# BBB_SCH2.net
KiCad netlist of a schematic drawn in Altium Designer
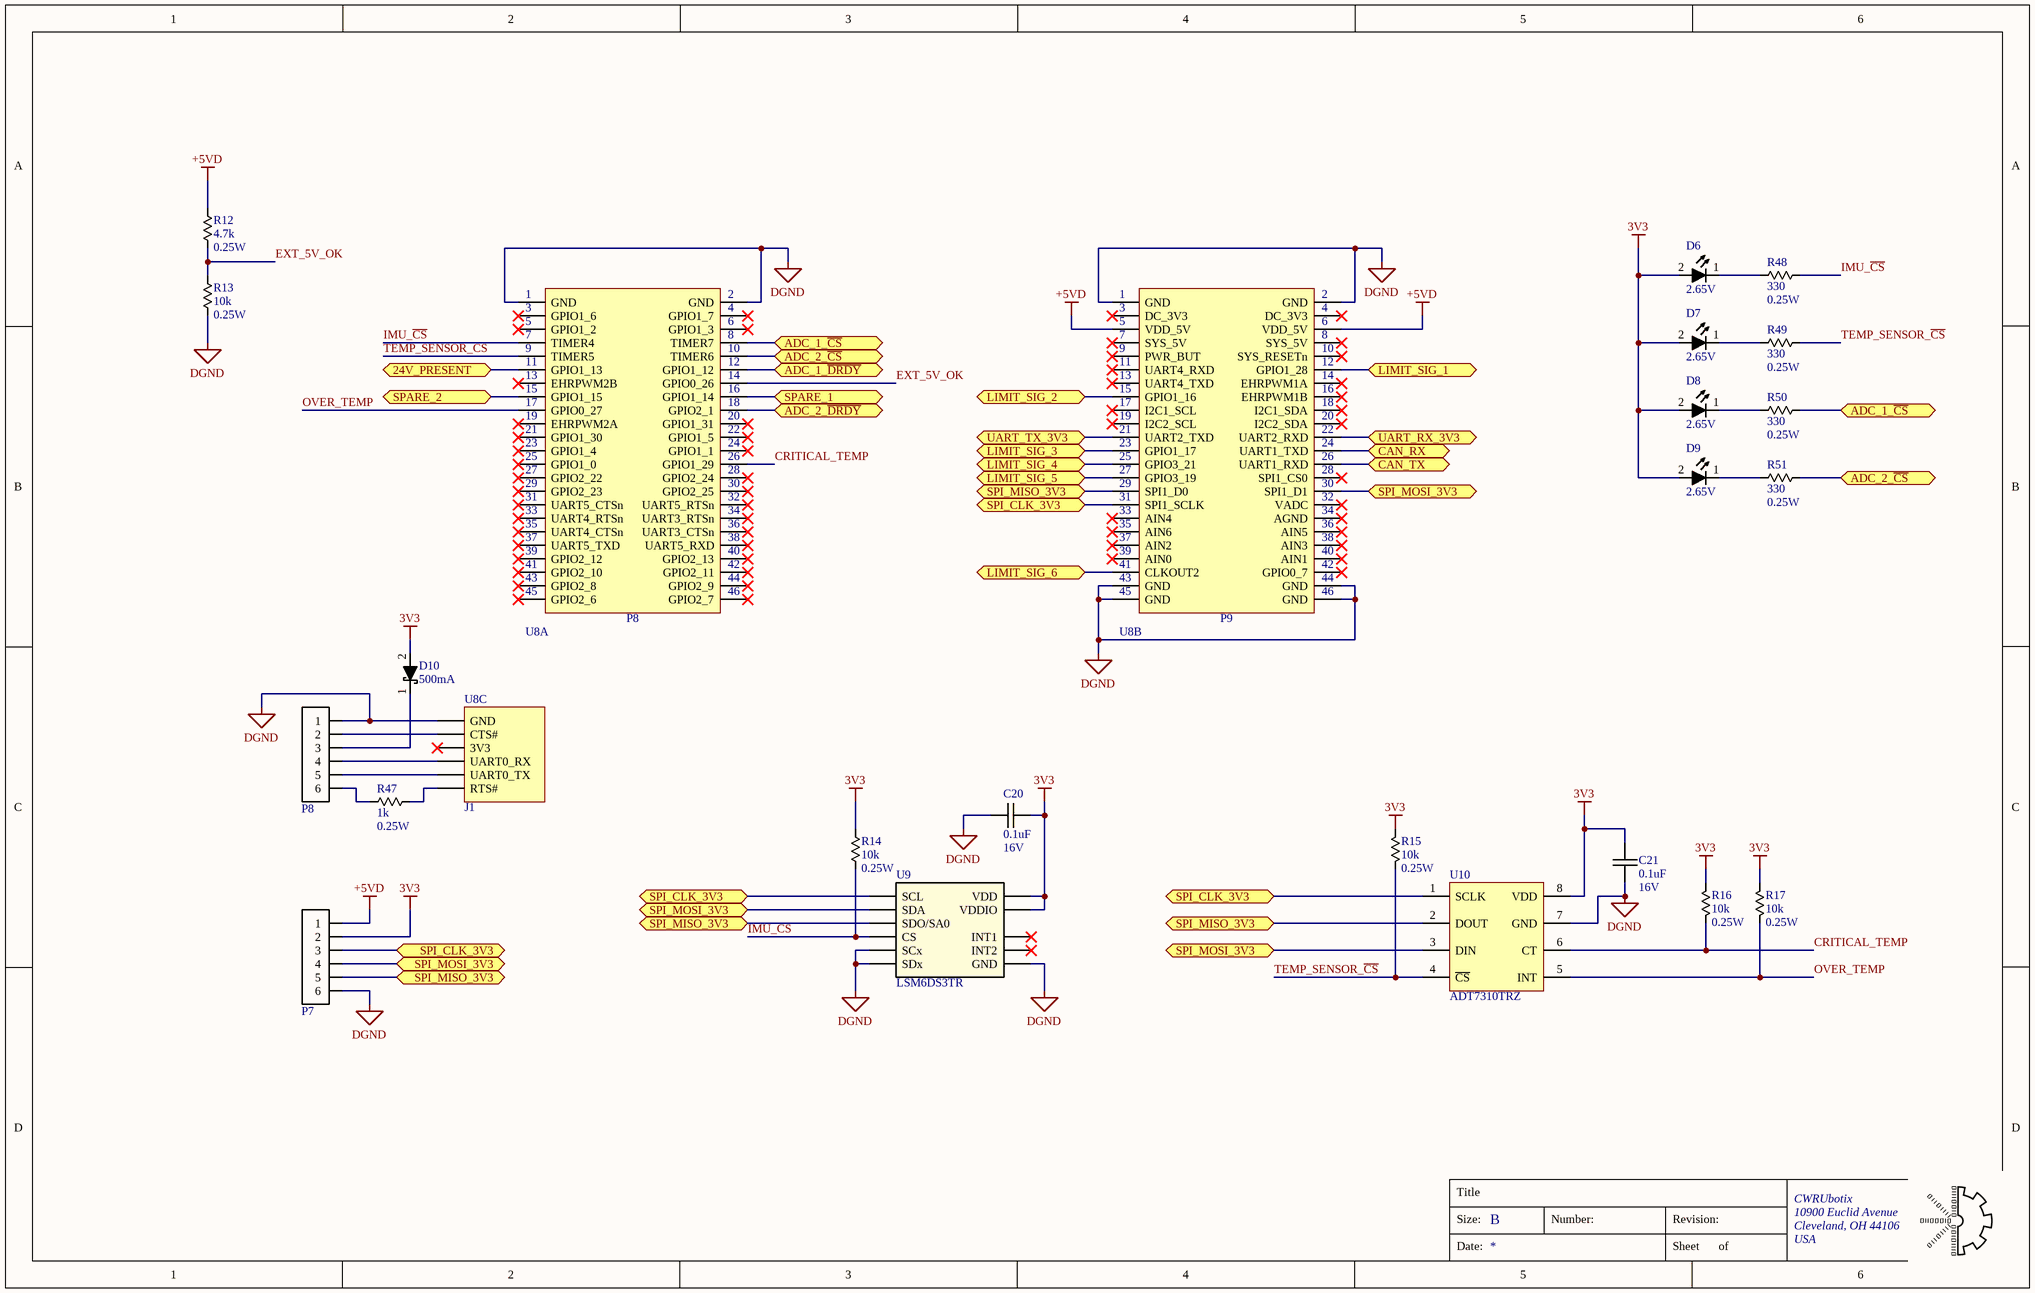
[diagram p0: BBB_SCH2.SchDoc]

(export (version "E")
  (design (tool "Eeschema 10.0.6"))
  (components
    (comp (ref "C20")
      (value "cap_single_np")
      (footprint "chip_0603")
      (description "CAP, 0.1uF, ±10%, 16V, X7R, 0603")
      (fields
        (field (name "TOLERANCE") "±10%")
        (field (name "CAPACITANCE") "0.1uF")
        (field (name "VOLTAGE RATING") "16V")
        (field (name "PART NUMBER") "CAP-00542")
      )
      (libsource (lib "Capacitors") (part "cap_single_np"))
    )
    (comp (ref "C21")
      (value "cap_single_np")
      (footprint "chip_0603")
      (description "CAP, 0.1uF, ±10%, 16V, X7R, 0603")
      (fields
        (field (name "TOLERANCE") "±10%")
        (field (name "CAPACITANCE") "0.1uF")
        (field (name "VOLTAGE RATING") "16V")
        (field (name "PART NUMBER") "CAP-00542")
      )
      (libsource (lib "Capacitors") (part "cap_single_np"))
    )
    (comp (ref "D6")
      (value "diode_4")
      (footprint "chip_0603")
      (description "LED, Blue, 0603, Low current, HELI2 Series")
      (fields
        (field (name "FORWARD VOLTAGE") "2.65V")
        (field (name "PART NUMBER") "DIO-00049")
        (field (name "MANUFACTURER") "Kingbright")
      )
      (libsource (lib "Diodes") (part "diode_4"))
    )
    (comp (ref "D7")
      (value "diode_4")
      (footprint "chip_0603")
      (description "LED, Blue, 0603, Low current, HELI2 Series")
      (fields
        (field (name "FORWARD VOLTAGE") "2.65V")
        (field (name "PART NUMBER") "DIO-00049")
        (field (name "MANUFACTURER") "Kingbright")
      )
      (libsource (lib "Diodes") (part "diode_4"))
    )
    (comp (ref "D8")
      (value "diode_4")
      (footprint "chip_0603")
      (description "LED, Blue, 0603, Low current, HELI2 Series")
      (fields
        (field (name "FORWARD VOLTAGE") "2.65V")
        (field (name "PART NUMBER") "DIO-00049")
        (field (name "MANUFACTURER") "Kingbright")
      )
      (libsource (lib "Diodes") (part "diode_4"))
    )
    (comp (ref "D9")
      (value "diode_4")
      (footprint "chip_0603")
      (description "LED, Blue, 0603, Low current, HELI2 Series")
      (fields
        (field (name "FORWARD VOLTAGE") "2.65V")
        (field (name "PART NUMBER") "DIO-00049")
        (field (name "MANUFACTURER") "Kingbright")
      )
      (libsource (lib "Diodes") (part "diode_4"))
    )
    (comp (ref "D10")
      (value "diode_2")
      (footprint "sod323_0")
      (description "Dio Shtky, 500mA, 0.62V, 30V, SOD-323")
      (fields
        (field (name "CURRENT RATING") "500mA")
        (field (name "PART NUMBER") "DIO-00000")
        (field (name "MANUFACTURER") "ON Semi")
      )
      (libsource (lib "Diodes") (part "diode_2"))
    )
    (comp (ref "P7")
      (value "conn-6x1_0")
      (footprint "HDDR_6X1_0")
      (description "Header 6x1, 0.1\"")
      (fields (field (name "PART NUMBER") "CONN-00008"))
      (libsource (lib "Connectors") (part "conn-6x1_0"))
    )
    (comp (ref "P8")
      (value "conn-6x1_0")
      (footprint "SOCK_6x1_0")
      (description "Female Socket, 6x1, 0.1\"")
      (fields (field (name "PART NUMBER") "CONN-00046") (field (name "MANUFACTURER") "Samtec"))
      (libsource (lib "Connectors") (part "conn-6x1_0"))
    )
    (comp (ref "R12")
      (value "res_single")
      (footprint "chip_0603")
      (description "RES SMD 4.7K OHM 1% 1/4W 0603")
      (fields
        (field (name "TOLERANCE") "1%")
        (field (name "RESISTANCE") "4.7k")
        (field (name "POWER RATING") "0.25W")
        (field (name "PART NUMBER") "RES-00470")
      )
      (libsource (lib "Resistors") (part "res_single"))
    )
    (comp (ref "R13")
      (value "res_single")
      (footprint "chip_0603")
      (description "RES SMD 10K OHM 1% 1/4W 0603")
      (fields
        (field (name "TOLERANCE") "1%")
        (field (name "RESISTANCE") "10k")
        (field (name "POWER RATING") "0.25W")
        (field (name "PART NUMBER") "RES-00306")
      )
      (libsource (lib "Resistors") (part "res_single"))
    )
    (comp (ref "R14")
      (value "res_single")
      (footprint "chip_0603")
      (description "RES SMD 10K OHM 1% 1/4W 0603")
      (fields
        (field (name "TOLERANCE") "1%")
        (field (name "RESISTANCE") "10k")
        (field (name "POWER RATING") "0.25W")
        (field (name "PART NUMBER") "RES-00306")
      )
      (libsource (lib "Resistors") (part "res_single"))
    )
    (comp (ref "R15")
      (value "res_single")
      (footprint "chip_0603")
      (description "RES SMD 10K OHM 1% 1/4W 0603")
      (fields
        (field (name "TOLERANCE") "1%")
        (field (name "RESISTANCE") "10k")
        (field (name "POWER RATING") "0.25W")
        (field (name "PART NUMBER") "RES-00306")
      )
      (libsource (lib "Resistors") (part "res_single"))
    )
    (comp (ref "R16")
      (value "res_single")
      (footprint "chip_0603")
      (description "RES SMD 10K OHM 1% 1/4W 0603")
      (fields
        (field (name "TOLERANCE") "1%")
        (field (name "RESISTANCE") "10k")
        (field (name "POWER RATING") "0.25W")
        (field (name "PART NUMBER") "RES-00306")
      )
      (libsource (lib "Resistors") (part "res_single"))
    )
    (comp (ref "R17")
      (value "res_single")
      (footprint "chip_0603")
      (description "RES SMD 10K OHM 1% 1/4W 0603")
      (fields
        (field (name "TOLERANCE") "1%")
        (field (name "RESISTANCE") "10k")
        (field (name "POWER RATING") "0.25W")
        (field (name "PART NUMBER") "RES-00306")
      )
      (libsource (lib "Resistors") (part "res_single"))
    )
    (comp (ref "R47")
      (value "res_single")
      (footprint "chip_0603")
      (description "RES SMD 1K OHM 1% 1/4W 0603")
      (fields
        (field (name "TOLERANCE") "1%")
        (field (name "RESISTANCE") "1k")
        (field (name "POWER RATING") "0.25W")
        (field (name "PART NUMBER") "RES-00360")
      )
      (libsource (lib "Resistors") (part "res_single"))
    )
    (comp (ref "R48")
      (value "res_single")
      (footprint "chip_0603")
      (description "RES SMD 330 OHM 1% 1/4W 0603")
      (fields
        (field (name "TOLERANCE") "1%")
        (field (name "RESISTANCE") "330")
        (field (name "POWER RATING") "0.25W")
        (field (name "PART NUMBER") "RES-00221")
      )
      (libsource (lib "Resistors") (part "res_single"))
    )
    (comp (ref "R49")
      (value "res_single")
      (footprint "chip_0603")
      (description "RES SMD 330 OHM 1% 1/4W 0603")
      (fields
        (field (name "TOLERANCE") "1%")
        (field (name "RESISTANCE") "330")
        (field (name "POWER RATING") "0.25W")
        (field (name "PART NUMBER") "RES-00221")
      )
      (libsource (lib "Resistors") (part "res_single"))
    )
    (comp (ref "R50")
      (value "res_single")
      (footprint "chip_0603")
      (description "RES SMD 330 OHM 1% 1/4W 0603")
      (fields
        (field (name "TOLERANCE") "1%")
        (field (name "RESISTANCE") "330")
        (field (name "POWER RATING") "0.25W")
        (field (name "PART NUMBER") "RES-00221")
      )
      (libsource (lib "Resistors") (part "res_single"))
    )
    (comp (ref "R51")
      (value "res_single")
      (footprint "chip_0603")
      (description "RES SMD 330 OHM 1% 1/4W 0603")
      (fields
        (field (name "TOLERANCE") "1%")
        (field (name "RESISTANCE") "330")
        (field (name "POWER RATING") "0.25W")
        (field (name "PART NUMBER") "RES-00221")
      )
      (libsource (lib "Resistors") (part "res_single"))
    )
    (comp (ref "U8")
      (value "BBB")
      (footprint "BEAGLEBONE")
      (description "Beaglebone Black")
      (fields (field (name "PART NUMBER") "MISC-00020"))
      (libsource (lib "Misc") (part "BBB"))
    )
    (comp (ref "U9")
      (value "LSM6DS3")
      (footprint "LGA14")
      (description "Accel & Gyro, 3-Axis, SPI/I2C")
      (fields
        (field (name "MANUFACTURER PN") "LSM6DS3TR")
        (field (name "PART NUMBER") "MISC-00012")
        (field (name "MANUFACTURER") "STM")
      )
      (libsource (lib "Misc") (part "LSM6DS3"))
    )
    (comp (ref "U10")
      (value "ADT7310")
      (footprint "SO-8")
      (description "IC, 0.5°C Accurate 16-bit Digital SPI Temperature Sensor, SOIC-8, ADT7310")
      (fields
        (field (name "MANUFACTURER PN") "ADT7310TRZ")
        (field (name "PART NUMBER") "ANLG-00048")
        (field (name "MANUFACTURER") "Analog Devices")
      )
      (libsource (lib "Analog") (part "ADT7310"))
    )
  )
  (nets
    (net (code "1") (name "+5VD") (class "Default")
      (node (ref "P7") (pin "1") (pinfunction "1_1") (pintype "passive"))
      (node (ref "R12") (pin "2") (pinfunction "2_2") (pintype "passive"))
      (node (ref "U8") (pin "51") (pinfunction "VDD_5V_51") (pintype "passive"))
      (node (ref "U8") (pin "52") (pinfunction "VDD_5V_52") (pintype "passive"))
    )
    (net (code "2") (name "/24V_PRESENT") (class "Default")
      (node (ref "U8") (pin "11") (pinfunction "GPIO1_13_11") (pintype "passive"))
    )
    (net (code "3") (name "/ADC_1_~{CS}") (class "Default")
      (node (ref "R50") (pin "2") (pinfunction "2_2") (pintype "passive"))
      (node (ref "U8") (pin "8") (pinfunction "TIMER7_8") (pintype "passive"))
    )
    (net (code "4") (name "/ADC_1_~{DRDY}") (class "Default")
      (node (ref "U8") (pin "12") (pinfunction "GPIO1_12_12") (pintype "passive"))
    )
    (net (code "5") (name "/ADC_2_~{CS}") (class "Default")
      (node (ref "R51") (pin "2") (pinfunction "2_2") (pintype "passive"))
      (node (ref "U8") (pin "10") (pinfunction "TIMER6_10") (pintype "passive"))
    )
    (net (code "6") (name "/ADC_2_~{DRDY}") (class "Default")
      (node (ref "U8") (pin "18") (pinfunction "GPIO2_1_18") (pintype "passive"))
    )
    (net (code "7") (name "/CAN_RX") (class "Default")
      (node (ref "U8") (pin "70") (pinfunction "UART1_TXD_70") (pintype "passive"))
    )
    (net (code "8") (name "/CAN_TX") (class "Default")
      (node (ref "U8") (pin "72") (pinfunction "UART1_RXD_72") (pintype "passive"))
    )
    (net (code "9") (name "/CRITICAL_TEMP") (class "Default")
      (node (ref "R16") (pin "2") (pinfunction "2_2") (pintype "passive"))
      (node (ref "U10") (pin "6") (pinfunction "CT_6") (pintype "passive"))
      (node (ref "U8") (pin "26") (pinfunction "GPIO1_29_26") (pintype "passive"))
    )
    (net (code "10") (name "/EXT_5V_OK") (class "Default")
      (node (ref "R12") (pin "1") (pinfunction "1_1") (pintype "passive"))
      (node (ref "R13") (pin "1") (pinfunction "1_1") (pintype "passive"))
      (node (ref "U8") (pin "14") (pinfunction "GPIO0_26_14") (pintype "passive"))
    )
    (net (code "11") (name "/IMU_~{CS}") (class "Default")
      (node (ref "R14") (pin "2") (pinfunction "2_2") (pintype "passive"))
      (node (ref "R48") (pin "2") (pinfunction "2_2") (pintype "passive"))
      (node (ref "U8") (pin "7") (pinfunction "TIMER4_7") (pintype "passive"))
      (node (ref "U9") (pin "12") (pinfunction "CS_12") (pintype "passive"))
    )
    (net (code "12") (name "/LIMIT_SIG_1") (class "Default")
      (node (ref "U8") (pin "58") (pinfunction "GPIO1_28_58") (pintype "passive"))
    )
    (net (code "13") (name "/LIMIT_SIG_2") (class "Default")
      (node (ref "U8") (pin "61") (pinfunction "GPIO1_16_61") (pintype "passive"))
    )
    (net (code "14") (name "/LIMIT_SIG_3") (class "Default")
      (node (ref "U8") (pin "69") (pinfunction "GPIO1_17_69") (pintype "passive"))
    )
    (net (code "15") (name "/LIMIT_SIG_4") (class "Default")
      (node (ref "U8") (pin "71") (pinfunction "GPIO3_21_71") (pintype "passive"))
    )
    (net (code "16") (name "/LIMIT_SIG_5") (class "Default")
      (node (ref "U8") (pin "73") (pinfunction "GPIO3_19_73") (pintype "passive"))
    )
    (net (code "17") (name "/LIMIT_SIG_6") (class "Default")
      (node (ref "U8") (pin "87") (pinfunction "CLKOUT2_87") (pintype "passive"))
    )
    (net (code "18") (name "/OVER_TEMP") (class "Default")
      (node (ref "R17") (pin "2") (pinfunction "2_2") (pintype "passive"))
      (node (ref "U10") (pin "5") (pinfunction "INT_5") (pintype "passive"))
      (node (ref "U8") (pin "17") (pinfunction "GPIO0_27_17") (pintype "passive"))
    )
    (net (code "19") (name "/SPARE_1") (class "Default")
      (node (ref "U8") (pin "16") (pinfunction "GPIO1_14_16") (pintype "passive"))
    )
    (net (code "20") (name "/SPARE_2") (class "Default")
      (node (ref "U8") (pin "15") (pinfunction "GPIO1_15_15") (pintype "passive"))
    )
    (net (code "21") (name "/SPI_CLK_3V3") (class "Default")
      (node (ref "P7") (pin "3") (pinfunction "3_3") (pintype "passive"))
      (node (ref "U10") (pin "1") (pinfunction "SCLK_1") (pintype "passive"))
      (node (ref "U8") (pin "77") (pinfunction "SPI1_SCLK_77") (pintype "passive"))
      (node (ref "U9") (pin "13") (pinfunction "SCL_13") (pintype "passive"))
    )
    (net (code "22") (name "/SPI_MISO_3V3") (class "Default")
      (node (ref "P7") (pin "5") (pinfunction "5_5") (pintype "passive"))
      (node (ref "U10") (pin "2") (pinfunction "DOUT_2") (pintype "passive"))
      (node (ref "U8") (pin "75") (pinfunction "SPI1_D0_75") (pintype "passive"))
      (node (ref "U9") (pin "1") (pinfunction "SDO/SA0_1") (pintype "passive"))
    )
    (net (code "23") (name "/SPI_MOSI_3V3") (class "Default")
      (node (ref "P7") (pin "4") (pinfunction "4_4") (pintype "passive"))
      (node (ref "U10") (pin "3") (pinfunction "DIN_3") (pintype "passive"))
      (node (ref "U8") (pin "76") (pinfunction "SPI1_D1_76") (pintype "passive"))
      (node (ref "U9") (pin "14") (pinfunction "SDA_14") (pintype "passive"))
    )
    (net (code "24") (name "/TEMP_SENSOR_~{CS}") (class "Default")
      (node (ref "R15") (pin "2") (pinfunction "2_2") (pintype "passive"))
      (node (ref "R49") (pin "2") (pinfunction "2_2") (pintype "passive"))
      (node (ref "U10") (pin "4") (pinfunction "~{CS}_4") (pintype "passive"))
      (node (ref "U8") (pin "9") (pinfunction "TIMER5_9") (pintype "passive"))
    )
    (net (code "25") (name "/UART_RX_3V3") (class "Default")
      (node (ref "U8") (pin "68") (pinfunction "UART2_RXD_68") (pintype "passive"))
    )
    (net (code "26") (name "/UART_TX_3V3") (class "Default")
      (node (ref "U8") (pin "67") (pinfunction "UART2_TXD_67") (pintype "passive"))
    )
    (net (code "27") (name "3V3") (class "Default")
      (node (ref "C20") (pin "2") (pinfunction "2_2") (pintype "passive"))
      (node (ref "C21") (pin "2") (pinfunction "2_2") (pintype "passive"))
      (node (ref "D10") (pin "2") (pinfunction "2_2") (pintype "passive"))
      (node (ref "D6") (pin "2") (pinfunction "2_2") (pintype "passive"))
      (node (ref "D7") (pin "2") (pinfunction "2_2") (pintype "passive"))
      (node (ref "D8") (pin "2") (pinfunction "2_2") (pintype "passive"))
      (node (ref "D9") (pin "2") (pinfunction "2_2") (pintype "passive"))
      (node (ref "P7") (pin "2") (pinfunction "2_2") (pintype "passive"))
      (node (ref "R14") (pin "1") (pinfunction "1_1") (pintype "passive"))
      (node (ref "R15") (pin "1") (pinfunction "1_1") (pintype "passive"))
      (node (ref "R16") (pin "1") (pinfunction "1_1") (pintype "passive"))
      (node (ref "R17") (pin "1") (pinfunction "1_1") (pintype "passive"))
      (node (ref "U10") (pin "8") (pinfunction "VDD_8") (pintype "passive"))
      (node (ref "U9") (pin "5") (pinfunction "VDDIO_5") (pintype "passive"))
      (node (ref "U9") (pin "8") (pinfunction "VDD_8") (pintype "passive"))
    )
    (net (code "28") (name "DGND") (class "Default")
      (node (ref "C20") (pin "1") (pinfunction "1_1") (pintype "passive"))
      (node (ref "C21") (pin "1") (pinfunction "1_1") (pintype "passive"))
      (node (ref "P7") (pin "6") (pinfunction "6_6") (pintype "passive"))
      (node (ref "P8") (pin "1") (pinfunction "1_1") (pintype "passive"))
      (node (ref "R13") (pin "2") (pinfunction "2_2") (pintype "passive"))
      (node (ref "U10") (pin "7") (pinfunction "GND_7") (pintype "passive"))
      (node (ref "U8") (pin "1") (pinfunction "GND_1") (pintype "passive"))
      (node (ref "U8") (pin "2") (pinfunction "GND_2") (pintype "passive"))
      (node (ref "U8") (pin "47") (pinfunction "GND_47") (pintype "passive"))
      (node (ref "U8") (pin "48") (pinfunction "GND_48") (pintype "passive"))
      (node (ref "U8") (pin "89") (pinfunction "GND_89") (pintype "passive"))
      (node (ref "U8") (pin "90") (pinfunction "GND_90") (pintype "passive"))
      (node (ref "U8") (pin "91") (pinfunction "GND_91") (pintype "passive"))
      (node (ref "U8") (pin "92") (pinfunction "GND_92") (pintype "passive"))
      (node (ref "U8") (pin "J1_1") (pinfunction "GND_J1_1") (pintype "passive"))
      (node (ref "U9") (pin "2") (pinfunction "SDx_2") (pintype "passive"))
      (node (ref "U9") (pin "3") (pinfunction "SCx_3") (pintype "passive"))
      (node (ref "U9") (pin "6") (pinfunction "GND_6") (pintype "passive"))
    )
    (net (code "29") (name "Net-(D6-Pad1)") (class "Default")
      (node (ref "D6") (pin "1") (pinfunction "1_1") (pintype "passive"))
      (node (ref "R48") (pin "1") (pinfunction "1_1") (pintype "passive"))
    )
    (net (code "30") (name "Net-(D7-Pad1)") (class "Default")
      (node (ref "D7") (pin "1") (pinfunction "1_1") (pintype "passive"))
      (node (ref "R49") (pin "1") (pinfunction "1_1") (pintype "passive"))
    )
    (net (code "31") (name "Net-(D8-Pad1)") (class "Default")
      (node (ref "D8") (pin "1") (pinfunction "1_1") (pintype "passive"))
      (node (ref "R50") (pin "1") (pinfunction "1_1") (pintype "passive"))
    )
    (net (code "32") (name "Net-(D9-Pad1)") (class "Default")
      (node (ref "D9") (pin "1") (pinfunction "1_1") (pintype "passive"))
      (node (ref "R51") (pin "1") (pinfunction "1_1") (pintype "passive"))
    )
    (net (code "33") (name "Net-(D10-Pad1)") (class "Default")
      (node (ref "D10") (pin "1") (pinfunction "1_1") (pintype "passive"))
      (node (ref "P8") (pin "3") (pinfunction "3_3") (pintype "passive"))
    )
    (net (code "34") (name "Net-(P8-Pad6)") (class "Default")
      (node (ref "P8") (pin "6") (pinfunction "6_6") (pintype "passive"))
      (node (ref "R47") (pin "1") (pinfunction "1_1") (pintype "passive"))
    )
    (net (code "35") (name "Net-(U8C-CTS#)") (class "Default")
      (node (ref "P8") (pin "2") (pinfunction "2_2") (pintype "passive"))
      (node (ref "U8") (pin "J1_2") (pinfunction "CTS#_J1_2") (pintype "passive"))
    )
    (net (code "36") (name "Net-(U8C-RTS#)") (class "Default")
      (node (ref "R47") (pin "2") (pinfunction "2_2") (pintype "passive"))
      (node (ref "U8") (pin "J1_6") (pinfunction "RTS#_J1_6") (pintype "passive"))
    )
    (net (code "37") (name "Net-(U8C-UART0_RX)") (class "Default")
      (node (ref "P8") (pin "4") (pinfunction "4_4") (pintype "passive"))
      (node (ref "U8") (pin "J1_4") (pinfunction "UART0_RX_J1_4") (pintype "passive"))
    )
    (net (code "38") (name "Net-(U8C-UART0_TX)") (class "Default")
      (node (ref "P8") (pin "5") (pinfunction "5_5") (pintype "passive"))
      (node (ref "U8") (pin "J1_5") (pinfunction "UART0_TX_J1_5") (pintype "passive"))
    )
    (net (code "39") (name "unconnected-(U8A-EHRPWM2A-Pad19)") (class "Default")
      (node (ref "U8") (pin "19") (pinfunction "EHRPWM2A_19") (pintype "passive+no_connect"))
    )
    (net (code "40") (name "unconnected-(U8A-EHRPWM2B-Pad13)") (class "Default")
      (node (ref "U8") (pin "13") (pinfunction "EHRPWM2B_13") (pintype "passive+no_connect"))
    )
    (net (code "41") (name "unconnected-(U8A-GPIO1_0-Pad25)") (class "Default")
      (node (ref "U8") (pin "25") (pinfunction "GPIO1_0_25") (pintype "passive+no_connect"))
    )
    (net (code "42") (name "unconnected-(U8A-GPIO1_1-Pad24)") (class "Default")
      (node (ref "U8") (pin "24") (pinfunction "GPIO1_1_24") (pintype "passive+no_connect"))
    )
    (net (code "43") (name "unconnected-(U8A-GPIO1_2-Pad5)") (class "Default")
      (node (ref "U8") (pin "5") (pinfunction "GPIO1_2_5") (pintype "passive+no_connect"))
    )
    (net (code "44") (name "unconnected-(U8A-GPIO1_3-Pad6)") (class "Default")
      (node (ref "U8") (pin "6") (pinfunction "GPIO1_3_6") (pintype "passive+no_connect"))
    )
    (net (code "45") (name "unconnected-(U8A-GPIO1_4-Pad23)") (class "Default")
      (node (ref "U8") (pin "23") (pinfunction "GPIO1_4_23") (pintype "passive+no_connect"))
    )
    (net (code "46") (name "unconnected-(U8A-GPIO1_5-Pad22)") (class "Default")
      (node (ref "U8") (pin "22") (pinfunction "GPIO1_5_22") (pintype "passive+no_connect"))
    )
    (net (code "47") (name "unconnected-(U8A-GPIO1_6-Pad3)") (class "Default")
      (node (ref "U8") (pin "3") (pinfunction "GPIO1_6_3") (pintype "passive+no_connect"))
    )
    (net (code "48") (name "unconnected-(U8A-GPIO1_7-Pad4)") (class "Default")
      (node (ref "U8") (pin "4") (pinfunction "GPIO1_7_4") (pintype "passive+no_connect"))
    )
    (net (code "49") (name "unconnected-(U8A-GPIO1_30-Pad21)") (class "Default")
      (node (ref "U8") (pin "21") (pinfunction "GPIO1_30_21") (pintype "passive+no_connect"))
    )
    (net (code "50") (name "unconnected-(U8A-GPIO1_31-Pad20)") (class "Default")
      (node (ref "U8") (pin "20") (pinfunction "GPIO1_31_20") (pintype "passive+no_connect"))
    )
    (net (code "51") (name "unconnected-(U8A-GPIO2_6-Pad45)") (class "Default")
      (node (ref "U8") (pin "45") (pinfunction "GPIO2_6_45") (pintype "passive+no_connect"))
    )
    (net (code "52") (name "unconnected-(U8A-GPIO2_7-Pad46)") (class "Default")
      (node (ref "U8") (pin "46") (pinfunction "GPIO2_7_46") (pintype "passive+no_connect"))
    )
    (net (code "53") (name "unconnected-(U8A-GPIO2_8-Pad43)") (class "Default")
      (node (ref "U8") (pin "43") (pinfunction "GPIO2_8_43") (pintype "passive+no_connect"))
    )
    (net (code "54") (name "unconnected-(U8A-GPIO2_9-Pad44)") (class "Default")
      (node (ref "U8") (pin "44") (pinfunction "GPIO2_9_44") (pintype "passive+no_connect"))
    )
    (net (code "55") (name "unconnected-(U8A-GPIO2_10-Pad41)") (class "Default")
      (node (ref "U8") (pin "41") (pinfunction "GPIO2_10_41") (pintype "passive+no_connect"))
    )
    (net (code "56") (name "unconnected-(U8A-GPIO2_11-Pad42)") (class "Default")
      (node (ref "U8") (pin "42") (pinfunction "GPIO2_11_42") (pintype "passive+no_connect"))
    )
    (net (code "57") (name "unconnected-(U8A-GPIO2_12-Pad39)") (class "Default")
      (node (ref "U8") (pin "39") (pinfunction "GPIO2_12_39") (pintype "passive+no_connect"))
    )
    (net (code "58") (name "unconnected-(U8A-GPIO2_13-Pad40)") (class "Default")
      (node (ref "U8") (pin "40") (pinfunction "GPIO2_13_40") (pintype "passive+no_connect"))
    )
    (net (code "59") (name "unconnected-(U8A-GPIO2_22-Pad27)") (class "Default")
      (node (ref "U8") (pin "27") (pinfunction "GPIO2_22_27") (pintype "passive+no_connect"))
    )
    (net (code "60") (name "unconnected-(U8A-GPIO2_23-Pad29)") (class "Default")
      (node (ref "U8") (pin "29") (pinfunction "GPIO2_23_29") (pintype "passive+no_connect"))
    )
    (net (code "61") (name "unconnected-(U8A-GPIO2_24-Pad28)") (class "Default")
      (node (ref "U8") (pin "28") (pinfunction "GPIO2_24_28") (pintype "passive+no_connect"))
    )
    (net (code "62") (name "unconnected-(U8A-GPIO2_25-Pad30)") (class "Default")
      (node (ref "U8") (pin "30") (pinfunction "GPIO2_25_30") (pintype "passive+no_connect"))
    )
    (net (code "63") (name "unconnected-(U8A-UART3_CTSn-Pad36)") (class "Default")
      (node (ref "U8") (pin "36") (pinfunction "UART3_CTSn_36") (pintype "passive+no_connect"))
    )
    (net (code "64") (name "unconnected-(U8A-UART3_RTSn-Pad34)") (class "Default")
      (node (ref "U8") (pin "34") (pinfunction "UART3_RTSn_34") (pintype "passive+no_connect"))
    )
    (net (code "65") (name "unconnected-(U8A-UART4_CTSn-Pad35)") (class "Default")
      (node (ref "U8") (pin "35") (pinfunction "UART4_CTSn_35") (pintype "passive+no_connect"))
    )
    (net (code "66") (name "unconnected-(U8A-UART4_RTSn-Pad33)") (class "Default")
      (node (ref "U8") (pin "33") (pinfunction "UART4_RTSn_33") (pintype "passive+no_connect"))
    )
    (net (code "67") (name "unconnected-(U8A-UART5_CTSn-Pad31)") (class "Default")
      (node (ref "U8") (pin "31") (pinfunction "UART5_CTSn_31") (pintype "passive+no_connect"))
    )
    (net (code "68") (name "unconnected-(U8A-UART5_RTSn-Pad32)") (class "Default")
      (node (ref "U8") (pin "32") (pinfunction "UART5_RTSn_32") (pintype "passive+no_connect"))
    )
    (net (code "69") (name "unconnected-(U8A-UART5_RXD-Pad38)") (class "Default")
      (node (ref "U8") (pin "38") (pinfunction "UART5_RXD_38") (pintype "passive+no_connect"))
    )
    (net (code "70") (name "unconnected-(U8A-UART5_TXD-Pad37)") (class "Default")
      (node (ref "U8") (pin "37") (pinfunction "UART5_TXD_37") (pintype "passive+no_connect"))
    )
    (net (code "71") (name "unconnected-(U8B-AGND-Pad80)") (class "Default")
      (node (ref "U8") (pin "80") (pinfunction "AGND_80") (pintype "passive+no_connect"))
    )
    (net (code "72") (name "unconnected-(U8B-AIN0-Pad85)") (class "Default")
      (node (ref "U8") (pin "85") (pinfunction "AIN0_85") (pintype "passive+no_connect"))
    )
    (net (code "73") (name "unconnected-(U8B-AIN1-Pad86)") (class "Default")
      (node (ref "U8") (pin "86") (pinfunction "AIN1_86") (pintype "passive+no_connect"))
    )
    (net (code "74") (name "unconnected-(U8B-AIN2-Pad83)") (class "Default")
      (node (ref "U8") (pin "83") (pinfunction "AIN2_83") (pintype "passive+no_connect"))
    )
    (net (code "75") (name "unconnected-(U8B-AIN3-Pad84)") (class "Default")
      (node (ref "U8") (pin "84") (pinfunction "AIN3_84") (pintype "passive+no_connect"))
    )
    (net (code "76") (name "unconnected-(U8B-AIN4-Pad79)") (class "Default")
      (node (ref "U8") (pin "79") (pinfunction "AIN4_79") (pintype "passive+no_connect"))
    )
    (net (code "77") (name "unconnected-(U8B-AIN5-Pad82)") (class "Default")
      (node (ref "U8") (pin "82") (pinfunction "AIN5_82") (pintype "passive+no_connect"))
    )
    (net (code "78") (name "unconnected-(U8B-AIN6-Pad81)") (class "Default")
      (node (ref "U8") (pin "81") (pinfunction "AIN6_81") (pintype "passive+no_connect"))
    )
    (net (code "79") (name "unconnected-(U8B-DC_3V3-Pad49)") (class "Default")
      (node (ref "U8") (pin "49") (pinfunction "DC_3V3_49") (pintype "passive+no_connect"))
    )
    (net (code "80") (name "unconnected-(U8B-DC_3V3-Pad50)") (class "Default")
      (node (ref "U8") (pin "50") (pinfunction "DC_3V3_50") (pintype "passive+no_connect"))
    )
    (net (code "81") (name "unconnected-(U8B-EHRPWM1A-Pad60)") (class "Default")
      (node (ref "U8") (pin "60") (pinfunction "EHRPWM1A_60") (pintype "passive+no_connect"))
    )
    (net (code "82") (name "unconnected-(U8B-EHRPWM1B-Pad62)") (class "Default")
      (node (ref "U8") (pin "62") (pinfunction "EHRPWM1B_62") (pintype "passive+no_connect"))
    )
    (net (code "83") (name "unconnected-(U8B-GPIO0_7-Pad88)") (class "Default")
      (node (ref "U8") (pin "88") (pinfunction "GPIO0_7_88") (pintype "passive+no_connect"))
    )
    (net (code "84") (name "unconnected-(U8B-I2C1_SCL-Pad63)") (class "Default")
      (node (ref "U8") (pin "63") (pinfunction "I2C1_SCL_63") (pintype "passive+no_connect"))
    )
    (net (code "85") (name "unconnected-(U8B-I2C1_SDA-Pad64)") (class "Default")
      (node (ref "U8") (pin "64") (pinfunction "I2C1_SDA_64") (pintype "passive+no_connect"))
    )
    (net (code "86") (name "unconnected-(U8B-I2C2_SCL-Pad65)") (class "Default")
      (node (ref "U8") (pin "65") (pinfunction "I2C2_SCL_65") (pintype "passive+no_connect"))
    )
    (net (code "87") (name "unconnected-(U8B-I2C2_SDA-Pad66)") (class "Default")
      (node (ref "U8") (pin "66") (pinfunction "I2C2_SDA_66") (pintype "passive+no_connect"))
    )
    (net (code "88") (name "unconnected-(U8B-PWR_BUT-Pad55)") (class "Default")
      (node (ref "U8") (pin "55") (pinfunction "PWR_BUT_55") (pintype "passive+no_connect"))
    )
    (net (code "89") (name "unconnected-(U8B-SPI1_CS0-Pad74)") (class "Default")
      (node (ref "U8") (pin "74") (pinfunction "SPI1_CS0_74") (pintype "passive+no_connect"))
    )
    (net (code "90") (name "unconnected-(U8B-SYS_5V-Pad53)") (class "Default")
      (node (ref "U8") (pin "53") (pinfunction "SYS_5V_53") (pintype "passive+no_connect"))
    )
    (net (code "91") (name "unconnected-(U8B-SYS_5V-Pad54)") (class "Default")
      (node (ref "U8") (pin "54") (pinfunction "SYS_5V_54") (pintype "passive+no_connect"))
    )
    (net (code "92") (name "unconnected-(U8B-SYS_RESETn-Pad56)") (class "Default")
      (node (ref "U8") (pin "56") (pinfunction "SYS_RESETn_56") (pintype "passive+no_connect"))
    )
    (net (code "93") (name "unconnected-(U8B-UART4_RXD-Pad57)") (class "Default")
      (node (ref "U8") (pin "57") (pinfunction "UART4_RXD_57") (pintype "passive+no_connect"))
    )
    (net (code "94") (name "unconnected-(U8B-UART4_TXD-Pad59)") (class "Default")
      (node (ref "U8") (pin "59") (pinfunction "UART4_TXD_59") (pintype "passive+no_connect"))
    )
    (net (code "95") (name "unconnected-(U8B-VADC-Pad78)") (class "Default")
      (node (ref "U8") (pin "78") (pinfunction "VADC_78") (pintype "passive+no_connect"))
    )
    (net (code "96") (name "unconnected-(U8C-3V3-PadJ1_3)") (class "Default")
      (node (ref "U8") (pin "J1_3") (pinfunction "3V3_J1_3") (pintype "passive+no_connect"))
    )
    (net (code "97") (name "unconnected-(U9-GND-Pad7)") (class "Default")
      (node (ref "U9") (pin "7") (pinfunction "GND_7") (pintype "passive"))
    )
    (net (code "98") (name "unconnected-(U9-INT1-Pad4)") (class "Default")
      (node (ref "U9") (pin "4") (pinfunction "INT1_4") (pintype "passive+no_connect"))
    )
    (net (code "99") (name "unconnected-(U9-INT2-Pad9)") (class "Default")
      (node (ref "U9") (pin "9") (pinfunction "INT2_9") (pintype "passive+no_connect"))
    )
    (net (code "100") (name "unconnected-(U9-NC-Pad10)") (class "Default")
      (node (ref "U9") (pin "10") (pinfunction "NC_10") (pintype "passive"))
    )
    (net (code "101") (name "unconnected-(U9-NC-Pad11)") (class "Default")
      (node (ref "U9") (pin "11") (pinfunction "NC_11") (pintype "passive"))
    )
  )
)
